# MicrophoneArray.net
KiCad netlist of a schematic drawn in Altium Designer
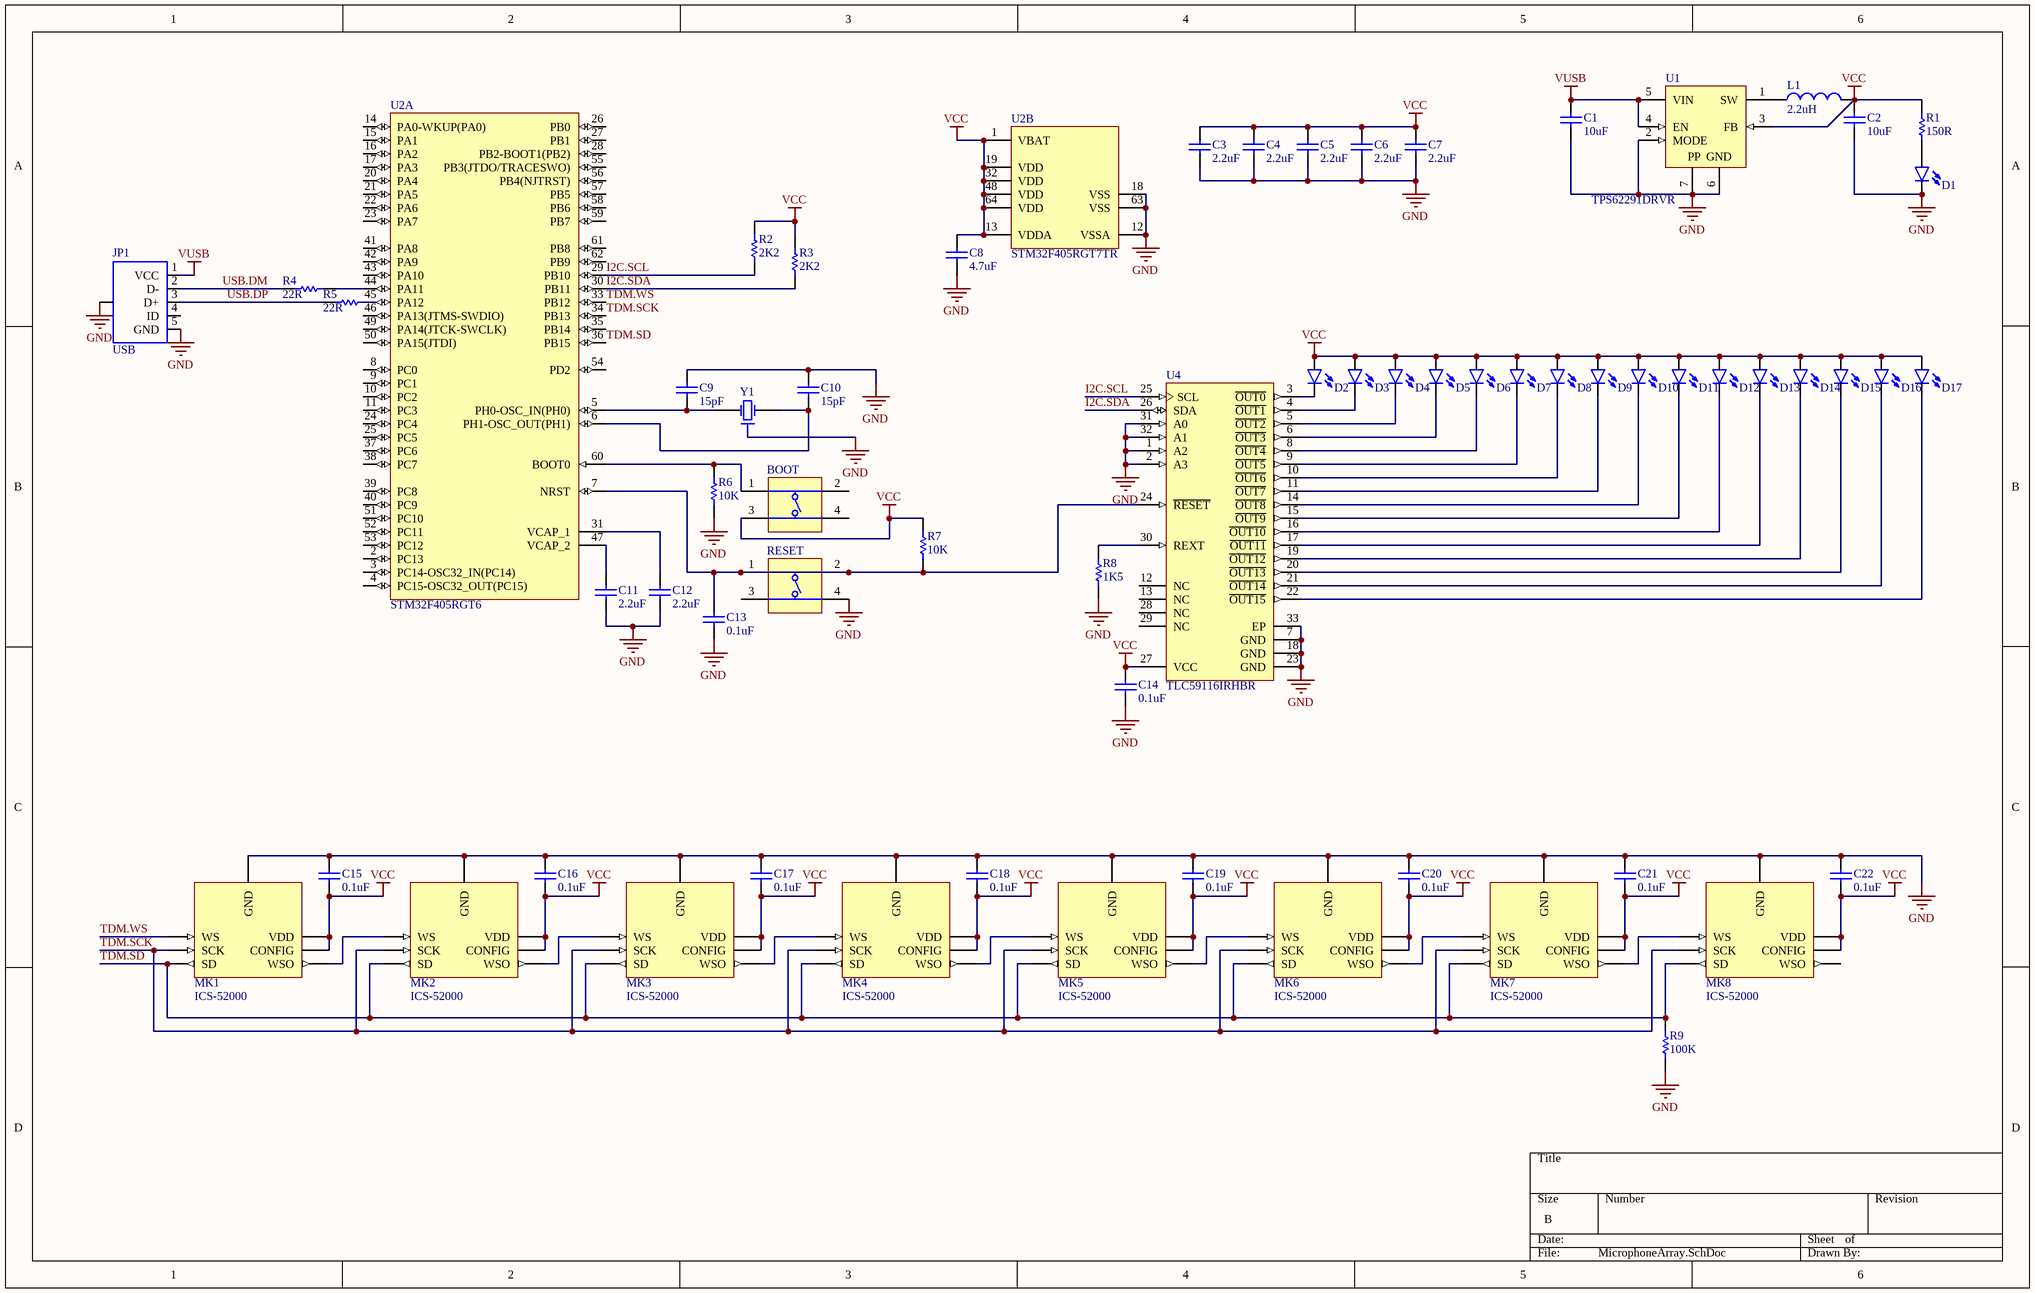
[diagram p0: MicrophoneArray.SchDoc]

(export (version "E")
  (design (tool "Eeschema 10.0.6"))
  (components
    (comp (ref "BOOT")
      (value "~")
      (footprint "SWITCH")
      (description "Switch, SPNO Push Button SMD")
      (fields
        (field (name "MANUFACTURER") "C&K Components")
        (field (name "PARTNUMBER") "PTS810 SJM 250 SMTR LFS")
      )
      (libsource (lib "Components") (part "DIPT-DTSM-6"))
    )
    (comp (ref "C1")
      (value "10uF")
      (footprint "C0402[1005X55]")
      (description "10uF 6.3V 20% 0402 (1005 Metric)")
      (fields (field (name "TOLERANCE") "20%") (field (name "PARTNUMBER") "GRM155R60J106ME44D"))
      (libsource (lib "Capacitors") (part "CAP_10uF_6.3V_0402_20%"))
    )
    (comp (ref "C2")
      (value "10uF")
      (footprint "C0402[1005X55]")
      (description "10uF 6.3V 20% 0402 (1005 Metric)")
      (fields (field (name "TOLERANCE") "20%") (field (name "PARTNUMBER") "GRM155R60J106ME44D"))
      (libsource (lib "Capacitors") (part "CAP_10uF_6.3V_0402_20%"))
    )
    (comp (ref "C3")
      (value "2.2uF")
      (footprint "C0402[1005X55]")
      (description "2.2uF 6.3V 20% 0402 (1005 Metric)")
      (fields (field (name "TOLERANCE") "20%") (field (name "PARTNUMBER") "GRM155R60J225ME15D"))
      (libsource (lib "Capacitors") (part "CAP_2.2uF_6.3V_0402_20%"))
    )
    (comp (ref "C4")
      (value "2.2uF")
      (footprint "C0402[1005X55]")
      (description "2.2uF 6.3V 20% 0402 (1005 Metric)")
      (fields (field (name "TOLERANCE") "20%") (field (name "PARTNUMBER") "GRM155R60J225ME15D"))
      (libsource (lib "Capacitors") (part "CAP_2.2uF_6.3V_0402_20%"))
    )
    (comp (ref "C5")
      (value "2.2uF")
      (footprint "C0402[1005X55]")
      (description "2.2uF 6.3V 20% 0402 (1005 Metric)")
      (fields (field (name "TOLERANCE") "20%") (field (name "PARTNUMBER") "GRM155R60J225ME15D"))
      (libsource (lib "Capacitors") (part "CAP_2.2uF_6.3V_0402_20%"))
    )
    (comp (ref "C6")
      (value "2.2uF")
      (footprint "C0402[1005X55]")
      (description "2.2uF 6.3V 20% 0402 (1005 Metric)")
      (fields (field (name "TOLERANCE") "20%") (field (name "PARTNUMBER") "GRM155R60J225ME15D"))
      (libsource (lib "Capacitors") (part "CAP_2.2uF_6.3V_0402_20%"))
    )
    (comp (ref "C7")
      (value "2.2uF")
      (footprint "C0402[1005X55]")
      (description "2.2uF 6.3V 20% 0402 (1005 Metric)")
      (fields (field (name "TOLERANCE") "20%") (field (name "PARTNUMBER") "GRM155R60J225ME15D"))
      (libsource (lib "Capacitors") (part "CAP_2.2uF_6.3V_0402_20%"))
    )
    (comp (ref "C8")
      (value "4.7uF")
      (footprint "C0402[1005X55]")
      (description "4.7uF 6.3V 20% 0402 (1005 Metric)")
      (fields (field (name "TOLERANCE") "20%") (field (name "PARTNUMBER") "GRM155R60J475ME47D"))
      (libsource (lib "Capacitors") (part "CAP_4.7uF_6.3V_0402_20%"))
    )
    (comp (ref "C9")
      (value "15pF")
      (footprint "C0402[1005X55]")
      (description "15pF 50V 5% 0402 (1005 Metric)")
      (fields (field (name "TOLERANCE") "5%") (field (name "PARTNUMBER") "GRM1555C1H150JA01D"))
      (libsource (lib "Capacitors") (part "CAP_15pF_50V_0402_5%"))
    )
    (comp (ref "C10")
      (value "15pF")
      (footprint "C0402[1005X55]")
      (description "15pF 50V 5% 0402 (1005 Metric)")
      (fields (field (name "TOLERANCE") "5%") (field (name "PARTNUMBER") "GRM1555C1H150JA01D"))
      (libsource (lib "Capacitors") (part "CAP_15pF_50V_0402_5%"))
    )
    (comp (ref "C11")
      (value "2.2uF")
      (footprint "C0402[1005X55]")
      (description "2.2uF 6.3V 20% 0402 (1005 Metric)")
      (fields (field (name "TOLERANCE") "20%") (field (name "PARTNUMBER") "GRM155R60J225ME15D"))
      (libsource (lib "Capacitors") (part "CAP_2.2uF_6.3V_0402_20%"))
    )
    (comp (ref "C12")
      (value "2.2uF")
      (footprint "C0402[1005X55]")
      (description "2.2uF 6.3V 20% 0402 (1005 Metric)")
      (fields (field (name "TOLERANCE") "20%") (field (name "PARTNUMBER") "GRM155R60J225ME15D"))
      (libsource (lib "Capacitors") (part "CAP_2.2uF_6.3V_0402_20%"))
    )
    (comp (ref "C13")
      (value "0.1uF")
      (footprint "C0402[1005X55]")
      (description "0.1uF 6.3V 10% 0402 (1005 Metric)")
      (fields (field (name "TOLERANCE") "10%") (field (name "PARTNUMBER") "GRM155R70J104KA01D"))
      (libsource (lib "Capacitors") (part "CAP_0.1uF_6.3V_0402_10%"))
    )
    (comp (ref "C14")
      (value "0.1uF")
      (footprint "C0402[1005X55]")
      (description "0.1uF 6.3V 10% 0402 (1005 Metric)")
      (fields (field (name "PARTNUMBER") "GRM155R70J104KA01D") (field (name "MANUFACTURER") "Murata"))
      (libsource (lib "Capacitors") (part "CAP_0.1uF_6.3V_0402_10%"))
    )
    (comp (ref "C15")
      (value "0.1uF")
      (footprint "C0402[1005X55]")
      (description "0.1uF 6.3V 10% 0402 (1005 Metric)")
      (fields (field (name "PARTNUMBER") "GRM155R70J104KA01D") (field (name "MANUFACTURER") "Murata"))
      (libsource (lib "Capacitors") (part "CAP_0.1uF_6.3V_0402_10%"))
    )
    (comp (ref "C16")
      (value "0.1uF")
      (footprint "C0402[1005X55]")
      (description "0.1uF 6.3V 10% 0402 (1005 Metric)")
      (fields (field (name "PARTNUMBER") "GRM155R70J104KA01D") (field (name "MANUFACTURER") "Murata"))
      (libsource (lib "Capacitors") (part "CAP_0.1uF_6.3V_0402_10%"))
    )
    (comp (ref "C17")
      (value "0.1uF")
      (footprint "C0402[1005X55]")
      (description "0.1uF 6.3V 10% 0402 (1005 Metric)")
      (fields (field (name "PARTNUMBER") "GRM155R70J104KA01D") (field (name "MANUFACTURER") "Murata"))
      (libsource (lib "Capacitors") (part "CAP_0.1uF_6.3V_0402_10%"))
    )
    (comp (ref "C18")
      (value "0.1uF")
      (footprint "C0402[1005X55]")
      (description "0.1uF 6.3V 10% 0402 (1005 Metric)")
      (fields (field (name "PARTNUMBER") "GRM155R70J104KA01D") (field (name "MANUFACTURER") "Murata"))
      (libsource (lib "Capacitors") (part "CAP_0.1uF_6.3V_0402_10%"))
    )
    (comp (ref "C19")
      (value "0.1uF")
      (footprint "C0402[1005X55]")
      (description "0.1uF 6.3V 10% 0402 (1005 Metric)")
      (fields (field (name "PARTNUMBER") "GRM155R70J104KA01D") (field (name "MANUFACTURER") "Murata"))
      (libsource (lib "Capacitors") (part "CAP_0.1uF_6.3V_0402_10%"))
    )
    (comp (ref "C20")
      (value "0.1uF")
      (footprint "C0402[1005X55]")
      (description "0.1uF 6.3V 10% 0402 (1005 Metric)")
      (fields (field (name "PARTNUMBER") "GRM155R70J104KA01D") (field (name "MANUFACTURER") "Murata"))
      (libsource (lib "Capacitors") (part "CAP_0.1uF_6.3V_0402_10%"))
    )
    (comp (ref "C21")
      (value "0.1uF")
      (footprint "C0402[1005X55]")
      (description "0.1uF 6.3V 10% 0402 (1005 Metric)")
      (fields (field (name "PARTNUMBER") "GRM155R70J104KA01D") (field (name "MANUFACTURER") "Murata"))
      (libsource (lib "Capacitors") (part "CAP_0.1uF_6.3V_0402_10%"))
    )
    (comp (ref "C22")
      (value "0.1uF")
      (footprint "C0402[1005X55]")
      (description "0.1uF 6.3V 10% 0402 (1005 Metric)")
      (fields (field (name "PARTNUMBER") "GRM155R70J104KA01D") (field (name "MANUFACTURER") "Murata"))
      (libsource (lib "Capacitors") (part "CAP_0.1uF_6.3V_0402_10%"))
    )
    (comp (ref "D1")
      (value "LED_0603_GREEN_5mA")
      (footprint "LED0603")
      (fields (field (name "PARTNUMBER") "LTST-C193TGKT-5A") (field (name "MANUFACTURER") "Lite-On Inc."))
      (libsource (lib "LEDs") (part "LED_0603_GREEN_5mA"))
    )
    (comp (ref "D2")
      (value "LED_0603_BLUE_5mA")
      (footprint "LED0603")
      (fields (field (name "PARTNUMBER") "LTST-C193TBKT-5A") (field (name "MANUFACTURER") "Lite-On Inc."))
      (libsource (lib "LEDs") (part "LED_0603_BLUE_5mA"))
    )
    (comp (ref "D3")
      (value "LED_0603_BLUE_5mA")
      (footprint "LED0603")
      (fields (field (name "PARTNUMBER") "LTST-C193TBKT-5A") (field (name "MANUFACTURER") "Lite-On Inc."))
      (libsource (lib "LEDs") (part "LED_0603_BLUE_5mA"))
    )
    (comp (ref "D4")
      (value "LED_0603_BLUE_5mA")
      (footprint "LED0603")
      (fields (field (name "PARTNUMBER") "LTST-C193TBKT-5A") (field (name "MANUFACTURER") "Lite-On Inc."))
      (libsource (lib "LEDs") (part "LED_0603_BLUE_5mA"))
    )
    (comp (ref "D5")
      (value "LED_0603_BLUE_5mA")
      (footprint "LED0603")
      (fields (field (name "PARTNUMBER") "LTST-C193TBKT-5A") (field (name "MANUFACTURER") "Lite-On Inc."))
      (libsource (lib "LEDs") (part "LED_0603_BLUE_5mA"))
    )
    (comp (ref "D6")
      (value "LED_0603_BLUE_5mA")
      (footprint "LED0603")
      (fields (field (name "PARTNUMBER") "LTST-C193TBKT-5A") (field (name "MANUFACTURER") "Lite-On Inc."))
      (libsource (lib "LEDs") (part "LED_0603_BLUE_5mA"))
    )
    (comp (ref "D7")
      (value "LED_0603_BLUE_5mA")
      (footprint "LED0603")
      (fields (field (name "PARTNUMBER") "LTST-C193TBKT-5A") (field (name "MANUFACTURER") "Lite-On Inc."))
      (libsource (lib "LEDs") (part "LED_0603_BLUE_5mA"))
    )
    (comp (ref "D8")
      (value "LED_0603_BLUE_5mA")
      (footprint "LED0603")
      (fields (field (name "PARTNUMBER") "LTST-C193TBKT-5A") (field (name "MANUFACTURER") "Lite-On Inc."))
      (libsource (lib "LEDs") (part "LED_0603_BLUE_5mA"))
    )
    (comp (ref "D9")
      (value "LED_0603_BLUE_5mA")
      (footprint "LED0603")
      (fields (field (name "PARTNUMBER") "LTST-C193TBKT-5A") (field (name "MANUFACTURER") "Lite-On Inc."))
      (libsource (lib "LEDs") (part "LED_0603_BLUE_5mA"))
    )
    (comp (ref "D10")
      (value "LED_0603_BLUE_5mA")
      (footprint "LED0603")
      (fields (field (name "PARTNUMBER") "LTST-C193TBKT-5A") (field (name "MANUFACTURER") "Lite-On Inc."))
      (libsource (lib "LEDs") (part "LED_0603_BLUE_5mA"))
    )
    (comp (ref "D11")
      (value "LED_0603_BLUE_5mA")
      (footprint "LED0603")
      (fields (field (name "PARTNUMBER") "LTST-C193TBKT-5A") (field (name "MANUFACTURER") "Lite-On Inc."))
      (libsource (lib "LEDs") (part "LED_0603_BLUE_5mA"))
    )
    (comp (ref "D12")
      (value "LED_0603_BLUE_5mA")
      (footprint "LED0603")
      (fields (field (name "PARTNUMBER") "LTST-C193TBKT-5A") (field (name "MANUFACTURER") "Lite-On Inc."))
      (libsource (lib "LEDs") (part "LED_0603_BLUE_5mA"))
    )
    (comp (ref "D13")
      (value "LED_0603_BLUE_5mA")
      (footprint "LED0603")
      (fields (field (name "PARTNUMBER") "LTST-C193TBKT-5A") (field (name "MANUFACTURER") "Lite-On Inc."))
      (libsource (lib "LEDs") (part "LED_0603_BLUE_5mA"))
    )
    (comp (ref "D14")
      (value "LED_0603_BLUE_5mA")
      (footprint "LED0603")
      (fields (field (name "PARTNUMBER") "LTST-C193TBKT-5A") (field (name "MANUFACTURER") "Lite-On Inc."))
      (libsource (lib "LEDs") (part "LED_0603_BLUE_5mA"))
    )
    (comp (ref "D15")
      (value "LED_0603_BLUE_5mA")
      (footprint "LED0603")
      (fields (field (name "PARTNUMBER") "LTST-C193TBKT-5A") (field (name "MANUFACTURER") "Lite-On Inc."))
      (libsource (lib "LEDs") (part "LED_0603_BLUE_5mA"))
    )
    (comp (ref "D16")
      (value "LED_0603_BLUE_5mA")
      (footprint "LED0603")
      (fields (field (name "PARTNUMBER") "LTST-C193TBKT-5A") (field (name "MANUFACTURER") "Lite-On Inc."))
      (libsource (lib "LEDs") (part "LED_0603_BLUE_5mA"))
    )
    (comp (ref "D17")
      (value "LED_0603_BLUE_5mA")
      (footprint "LED0603")
      (fields (field (name "PARTNUMBER") "LTST-C193TBKT-5A") (field (name "MANUFACTURER") "Lite-On Inc."))
      (libsource (lib "LEDs") (part "LED_0603_BLUE_5mA"))
    )
    (comp (ref "JP1")
      (value "USB")
      (footprint "USB-MICROB")
      (fields (field (name "PARTNUMBER") "10118192-0001LF") (field (name "MANUFACTURER") "Amphenol FCI"))
      (libsource (lib "Connectors") (part "USB_MICROB_SMT"))
    )
    (comp (ref "L1")
      (value "2.2uH")
      (footprint "IND0805")
      (description "2.2uH 20% 1.7A 0805")
      (fields (field (name "PARTNUMBER") "LQM21PN2R2MGHL") (field (name "MANUFACTURER") "Murata"))
      (libsource (lib "Inductors") (part "IND_2.2uH_1.7A_0805_20%"))
    )
    (comp (ref "MK1")
      (value "ICS-52000")
      (footprint "MIC")
      (description "MIC MEMS DIGITAL OMNI -26DB")
      (fields (field (name "MANUFACTURER") "TDK InvenSense"))
      (libsource (lib "Components") (part "ICS-52000"))
    )
    (comp (ref "MK2")
      (value "ICS-52000")
      (footprint "MIC")
      (description "MIC MEMS DIGITAL OMNI -26DB")
      (fields (field (name "MANUFACTURER") "TDK InvenSense"))
      (libsource (lib "Components") (part "ICS-52000"))
    )
    (comp (ref "MK3")
      (value "ICS-52000")
      (footprint "MIC")
      (description "MIC MEMS DIGITAL OMNI -26DB")
      (fields (field (name "MANUFACTURER") "TDK InvenSense"))
      (libsource (lib "Components") (part "ICS-52000"))
    )
    (comp (ref "MK4")
      (value "ICS-52000")
      (footprint "MIC")
      (description "MIC MEMS DIGITAL OMNI -26DB")
      (fields (field (name "MANUFACTURER") "TDK InvenSense"))
      (libsource (lib "Components") (part "ICS-52000"))
    )
    (comp (ref "MK5")
      (value "ICS-52000")
      (footprint "MIC")
      (description "MIC MEMS DIGITAL OMNI -26DB")
      (fields (field (name "MANUFACTURER") "TDK InvenSense"))
      (libsource (lib "Components") (part "ICS-52000"))
    )
    (comp (ref "MK6")
      (value "ICS-52000")
      (footprint "MIC")
      (description "MIC MEMS DIGITAL OMNI -26DB")
      (fields (field (name "MANUFACTURER") "TDK InvenSense"))
      (libsource (lib "Components") (part "ICS-52000"))
    )
    (comp (ref "MK7")
      (value "ICS-52000")
      (footprint "MIC")
      (description "MIC MEMS DIGITAL OMNI -26DB")
      (fields (field (name "MANUFACTURER") "TDK InvenSense"))
      (libsource (lib "Components") (part "ICS-52000"))
    )
    (comp (ref "MK8")
      (value "ICS-52000")
      (footprint "MIC")
      (description "MIC MEMS DIGITAL OMNI -26DB")
      (fields (field (name "MANUFACTURER") "TDK InvenSense"))
      (libsource (lib "Components") (part "ICS-52000"))
    )
    (comp (ref "R1")
      (value "150R")
      (footprint "R0402[1005]")
      (description "150R 0.063W 1% 0402 (1005 Metric)")
      (fields (field (name "MANUFACTURER") "KOA Speer") (field (name "PARTNUMBER") "RK73H1ETTP1500F"))
      (libsource (lib "Resistors") (part "RES_150R_0402_1%"))
    )
    (comp (ref "R2")
      (value "2K2")
      (footprint "R0402[1005]")
      (description "2K2 0.063W 1% 0402 (1005 Metric)")
      (fields (field (name "TOLERANCE") "1%") (field (name "POWER") "0.063W"))
      (libsource (lib "Resistors") (part "RES_2K2_0402_1%"))
    )
    (comp (ref "R3")
      (value "2K2")
      (footprint "R0402[1005]")
      (description "2K2 0.063W 1% 0402 (1005 Metric)")
      (fields (field (name "TOLERANCE") "1%") (field (name "POWER") "0.063W"))
      (libsource (lib "Resistors") (part "RES_2K2_0402_1%"))
    )
    (comp (ref "R4")
      (value "22R")
      (footprint "R0402[1005]")
      (description "22R 0.063W 1% 0402 (1005 Metric)")
      (fields (field (name "POWER") "0.063W") (field (name "TOLERANCE") "1%"))
      (libsource (lib "Resistors") (part "RES_22R_0402_1%"))
    )
    (comp (ref "R5")
      (value "22R")
      (footprint "R0402[1005]")
      (description "22R 0.063W 1% 0402 (1005 Metric)")
      (fields (field (name "POWER") "0.063W") (field (name "TOLERANCE") "1%"))
      (libsource (lib "Resistors") (part "RES_22R_0402_1%"))
    )
    (comp (ref "R6")
      (value "10K")
      (footprint "R0402[1005]")
      (description "10K 0.063W 1% 0402 (1005 Metric)")
      (fields (field (name "TOLERANCE") "1%") (field (name "POWER") "0.063W"))
      (libsource (lib "Resistors") (part "RES_10K_0402_1%"))
    )
    (comp (ref "R7")
      (value "10K")
      (footprint "R0402[1005]")
      (description "10K 0.063W 1% 0402 (1005 Metric)")
      (fields (field (name "MANUFACTURER") "KOA Speer") (field (name "PARTNUMBER") "RK73H1ETTP1002F"))
      (libsource (lib "Resistors") (part "RES_10K_0402_1%"))
    )
    (comp (ref "R8")
      (value "1K5")
      (footprint "R0402[1005]")
      (description "1K5 0.063W 1% 0402 (1005 Metric)")
      (fields (field (name "MANUFACTURER") "KOA Speer") (field (name "PARTNUMBER") "RK73H1ETTP1501F"))
      (libsource (lib "Resistors") (part "RES_1K5_0402_1%"))
    )
    (comp (ref "R9")
      (value "100K")
      (footprint "R0402[1005]")
      (description "100K 0.063W 1% 0402 (1005 Metric)")
      (fields (field (name "MANUFACTURER") "KOA Speer") (field (name "PARTNUMBER") "RK73H1ETTP1003F"))
      (libsource (lib "Resistors") (part "RES_100K_0402_1%"))
    )
    (comp (ref "RESET")
      (value "~")
      (footprint "SWITCH")
      (description "Switch, SPNO Push Button SMD")
      (fields
        (field (name "MANUFACTURER") "C&K Components")
        (field (name "PARTNUMBER") "PTS810 SJM 250 SMTR LFS")
      )
      (libsource (lib "Components") (part "DIPT-DTSM-6"))
    )
    (comp (ref "U1")
      (value "TPS62291DRVR")
      (footprint "WSON-6")
      (description "Voltage Regulators - Switching Regulators 2.25MHz 1A Step-Down Cnvrtr 3.3V Output")
      (fields (field (name "MANUFACTURER") "Texas Instruments"))
      (libsource (lib "ICs") (part "TPS62291DRVR"))
    )
    (comp (ref "U2")
      (value "STM32F405RGT6")
      (footprint "STM-LQFP64_L")
      (fields (field (name "MANUFACTURER") "STMicroelectronics"))
      (libsource (lib "Altium Content Vault") (part "CMP-0243-00089-2"))
    )
    (comp (ref "U4")
      (value "TLC59116IRHBR")
      (footprint "RHB0032E_V")
      (fields (field (name "MANUFACTURER") "Texas Instruments"))
      (libsource (lib "Altium Content Vault") (part "TI-TLC59116RHB32-3450X3450TP"))
    )
    (comp (ref "Y1")
      (value "~")
      (footprint "ABRA-ABM3B-4_V")
      (fields (field (name "PARTNUMBER") "ABM3B-8.000MHZ-10-1UT") (field (name "MANUFACTURER") "ABRACON"))
      (libsource (lib "Components") (part "ABRA-ABM3B-4"))
    )
  )
  (nets
    (net (code "1") (name "/I2C.SCL") (class "Default")
      (node (ref "R2") (pin "1") (pinfunction "1_1") (pintype "passive"))
      (node (ref "U2") (pin "29") (pinfunction "PB10_29") (pintype "bidirectional"))
      (node (ref "U4") (pin "25") (pinfunction "SCL_25") (pintype "input"))
    )
    (net (code "2") (name "/I2C.SDA") (class "Default")
      (node (ref "R3") (pin "1") (pinfunction "1_1") (pintype "passive"))
      (node (ref "U2") (pin "30") (pinfunction "PB11_30") (pintype "bidirectional"))
      (node (ref "U4") (pin "26") (pinfunction "SDA_26") (pintype "bidirectional"))
    )
    (net (code "3") (name "/TDM.SCK") (class "Default")
      (node (ref "MK1") (pin "6") (pinfunction "SCK_6") (pintype "input"))
      (node (ref "MK2") (pin "6") (pinfunction "SCK_6") (pintype "input"))
      (node (ref "MK3") (pin "6") (pinfunction "SCK_6") (pintype "input"))
      (node (ref "MK4") (pin "6") (pinfunction "SCK_6") (pintype "input"))
      (node (ref "MK5") (pin "6") (pinfunction "SCK_6") (pintype "input"))
      (node (ref "MK6") (pin "6") (pinfunction "SCK_6") (pintype "input"))
      (node (ref "MK7") (pin "6") (pinfunction "SCK_6") (pintype "input"))
      (node (ref "MK8") (pin "6") (pinfunction "SCK_6") (pintype "input"))
      (node (ref "U2") (pin "34") (pinfunction "PB13_34") (pintype "bidirectional"))
    )
    (net (code "4") (name "/TDM.SD") (class "Default")
      (node (ref "MK1") (pin "7") (pinfunction "SD_7") (pintype "output"))
      (node (ref "MK2") (pin "7") (pinfunction "SD_7") (pintype "output"))
      (node (ref "MK3") (pin "7") (pinfunction "SD_7") (pintype "output"))
      (node (ref "MK4") (pin "7") (pinfunction "SD_7") (pintype "output"))
      (node (ref "MK5") (pin "7") (pinfunction "SD_7") (pintype "output"))
      (node (ref "MK6") (pin "7") (pinfunction "SD_7") (pintype "output"))
      (node (ref "MK7") (pin "7") (pinfunction "SD_7") (pintype "output"))
      (node (ref "MK8") (pin "7") (pinfunction "SD_7") (pintype "output"))
      (node (ref "R9") (pin "2") (pinfunction "2_2") (pintype "passive"))
      (node (ref "U2") (pin "36") (pinfunction "PB15_36") (pintype "bidirectional"))
    )
    (net (code "5") (name "/TDM.WS") (class "Default")
      (node (ref "MK1") (pin "5") (pinfunction "WS_5") (pintype "input"))
      (node (ref "U2") (pin "33") (pinfunction "PB12_33") (pintype "bidirectional"))
    )
    (net (code "6") (name "/USB.DM") (class "Default")
      (node (ref "JP1") (pin "2") (pinfunction "D-_2") (pintype "passive"))
      (node (ref "R4") (pin "1") (pinfunction "1_1") (pintype "passive"))
    )
    (net (code "7") (name "/USB.DP") (class "Default")
      (node (ref "JP1") (pin "3") (pinfunction "D+_3") (pintype "passive"))
      (node (ref "R5") (pin "1") (pinfunction "1_1") (pintype "passive"))
    )
    (net (code "8") (name "GND") (class "Default")
      (node (ref "C1") (pin "1") (pinfunction "1_1") (pintype "passive"))
      (node (ref "C10") (pin "2") (pinfunction "2_2") (pintype "passive"))
      (node (ref "C11") (pin "1") (pinfunction "1_1") (pintype "passive"))
      (node (ref "C12") (pin "1") (pinfunction "1_1") (pintype "passive"))
      (node (ref "C13") (pin "1") (pinfunction "1_1") (pintype "passive"))
      (node (ref "C14") (pin "1") (pinfunction "1_1") (pintype "passive"))
      (node (ref "C15") (pin "2") (pinfunction "2_2") (pintype "passive"))
      (node (ref "C16") (pin "2") (pinfunction "2_2") (pintype "passive"))
      (node (ref "C17") (pin "2") (pinfunction "2_2") (pintype "passive"))
      (node (ref "C18") (pin "2") (pinfunction "2_2") (pintype "passive"))
      (node (ref "C19") (pin "2") (pinfunction "2_2") (pintype "passive"))
      (node (ref "C2") (pin "1") (pinfunction "1_1") (pintype "passive"))
      (node (ref "C20") (pin "2") (pinfunction "2_2") (pintype "passive"))
      (node (ref "C21") (pin "2") (pinfunction "2_2") (pintype "passive"))
      (node (ref "C22") (pin "2") (pinfunction "2_2") (pintype "passive"))
      (node (ref "C3") (pin "1") (pinfunction "1_1") (pintype "passive"))
      (node (ref "C4") (pin "1") (pinfunction "1_1") (pintype "passive"))
      (node (ref "C5") (pin "1") (pinfunction "1_1") (pintype "passive"))
      (node (ref "C6") (pin "1") (pinfunction "1_1") (pintype "passive"))
      (node (ref "C7") (pin "1") (pinfunction "1_1") (pintype "passive"))
      (node (ref "C8") (pin "1") (pinfunction "1_1") (pintype "passive"))
      (node (ref "C9") (pin "2") (pinfunction "2_2") (pintype "passive"))
      (node (ref "D1") (pin "C") (pinfunction "C_C") (pintype "passive"))
      (node (ref "JP1") (pin "5") (pinfunction "GND_5") (pintype "passive"))
      (node (ref "JP1") (pin "6") (pinfunction "SHIELD_6") (pintype "passive"))
      (node (ref "MK1") (pin "4") (pinfunction "GND_4") (pintype "power_in"))
      (node (ref "MK2") (pin "4") (pinfunction "GND_4") (pintype "power_in"))
      (node (ref "MK3") (pin "4") (pinfunction "GND_4") (pintype "power_in"))
      (node (ref "MK4") (pin "4") (pinfunction "GND_4") (pintype "power_in"))
      (node (ref "MK5") (pin "4") (pinfunction "GND_4") (pintype "power_in"))
      (node (ref "MK6") (pin "4") (pinfunction "GND_4") (pintype "power_in"))
      (node (ref "MK7") (pin "4") (pinfunction "GND_4") (pintype "power_in"))
      (node (ref "MK8") (pin "4") (pinfunction "GND_4") (pintype "power_in"))
      (node (ref "R6") (pin "1") (pinfunction "1_1") (pintype "passive"))
      (node (ref "R8") (pin "1") (pinfunction "1_1") (pintype "passive"))
      (node (ref "R9") (pin "1") (pinfunction "1_1") (pintype "passive"))
      (node (ref "RESET") (pin "4") (pinfunction "T3_4") (pintype "passive"))
      (node (ref "U1") (pin "2") (pinfunction "MODE_2") (pintype "input"))
      (node (ref "U1") (pin "6") (pinfunction "GND_6") (pintype "power_in"))
      (node (ref "U1") (pin "7") (pinfunction "EP_7") (pintype "passive"))
      (node (ref "U2") (pin "12") (pinfunction "VSSA_12") (pintype "power_in"))
      (node (ref "U2") (pin "18") (pinfunction "VSS_18") (pintype "power_in"))
      (node (ref "U2") (pin "63") (pinfunction "VSS_63") (pintype "power_in"))
      (node (ref "U4") (pin "1") (pinfunction "A2_1") (pintype "input"))
      (node (ref "U4") (pin "18") (pinfunction "GND_18") (pintype "power_in"))
      (node (ref "U4") (pin "2") (pinfunction "A3_2") (pintype "input"))
      (node (ref "U4") (pin "23") (pinfunction "GND_23") (pintype "power_in"))
      (node (ref "U4") (pin "31") (pinfunction "A0_31") (pintype "input"))
      (node (ref "U4") (pin "32") (pinfunction "A1_32") (pintype "input"))
      (node (ref "U4") (pin "33") (pinfunction "EP_33") (pintype "power_in"))
      (node (ref "U4") (pin "7") (pinfunction "GND_7") (pintype "power_in"))
      (node (ref "Y1") (pin "2") (pinfunction "2_2") (pintype "passive"))
    )
    (net (code "9") (name "Net-(BOOT-T1)") (class "Default")
      (node (ref "BOOT") (pin "1") (pinfunction "T1_1") (pintype "passive"))
      (node (ref "R6") (pin "2") (pinfunction "2_2") (pintype "passive"))
      (node (ref "U2") (pin "60") (pinfunction "BOOT0_60") (pintype "input"))
    )
    (net (code "10") (name "Net-(D1-PadA)") (class "Default")
      (node (ref "D1") (pin "A") (pinfunction "A_A") (pintype "passive"))
      (node (ref "R1") (pin "1") (pinfunction "1_1") (pintype "passive"))
    )
    (net (code "11") (name "Net-(MK1-WSO)") (class "Default")
      (node (ref "MK1") (pin "1") (pinfunction "WSO_1") (pintype "output"))
      (node (ref "MK2") (pin "5") (pinfunction "WS_5") (pintype "input"))
    )
    (net (code "12") (name "Net-(MK2-WSO)") (class "Default")
      (node (ref "MK2") (pin "1") (pinfunction "WSO_1") (pintype "output"))
      (node (ref "MK3") (pin "5") (pinfunction "WS_5") (pintype "input"))
    )
    (net (code "13") (name "Net-(MK3-WSO)") (class "Default")
      (node (ref "MK3") (pin "1") (pinfunction "WSO_1") (pintype "output"))
      (node (ref "MK4") (pin "5") (pinfunction "WS_5") (pintype "input"))
    )
    (net (code "14") (name "Net-(MK4-WSO)") (class "Default")
      (node (ref "MK4") (pin "1") (pinfunction "WSO_1") (pintype "output"))
      (node (ref "MK5") (pin "5") (pinfunction "WS_5") (pintype "input"))
    )
    (net (code "15") (name "Net-(MK5-WSO)") (class "Default")
      (node (ref "MK5") (pin "1") (pinfunction "WSO_1") (pintype "output"))
      (node (ref "MK6") (pin "5") (pinfunction "WS_5") (pintype "input"))
    )
    (net (code "16") (name "Net-(MK6-WSO)") (class "Default")
      (node (ref "MK6") (pin "1") (pinfunction "WSO_1") (pintype "output"))
      (node (ref "MK7") (pin "5") (pinfunction "WS_5") (pintype "input"))
    )
    (net (code "17") (name "Net-(MK7-WSO)") (class "Default")
      (node (ref "MK7") (pin "1") (pinfunction "WSO_1") (pintype "output"))
      (node (ref "MK8") (pin "5") (pinfunction "WS_5") (pintype "input"))
    )
    (net (code "18") (name "Net-(RESET-T1)") (class "Default")
      (node (ref "C13") (pin "2") (pinfunction "2_2") (pintype "passive"))
      (node (ref "R7") (pin "1") (pinfunction "1_1") (pintype "passive"))
      (node (ref "RESET") (pin "1") (pinfunction "T1_1") (pintype "passive"))
      (node (ref "RESET") (pin "2") (pinfunction "T2_2") (pintype "passive"))
      (node (ref "U2") (pin "7") (pinfunction "NRST_7") (pintype "bidirectional"))
      (node (ref "U4") (pin "24") (pinfunction "~{RESET}_24") (pintype "input"))
    )
    (net (code "19") (name "Net-(U1-SW)") (class "Default")
      (node (ref "L1") (pin "1") (pinfunction "1_1") (pintype "passive"))
      (node (ref "U1") (pin "1") (pinfunction "SW_1") (pintype "power_in"))
    )
    (net (code "20") (name "Net-(U2A-PA11)") (class "Default")
      (node (ref "R4") (pin "2") (pinfunction "2_2") (pintype "passive"))
      (node (ref "U2") (pin "44") (pinfunction "PA11_44") (pintype "bidirectional"))
    )
    (net (code "21") (name "Net-(U2A-PA12)") (class "Default")
      (node (ref "R5") (pin "2") (pinfunction "2_2") (pintype "passive"))
      (node (ref "U2") (pin "45") (pinfunction "PA12_45") (pintype "bidirectional"))
    )
    (net (code "22") (name "Net-(U2A-PH0-OSC_IN(PH0))") (class "Default")
      (node (ref "C9") (pin "1") (pinfunction "1_1") (pintype "passive"))
      (node (ref "U2") (pin "5") (pinfunction "PH0-OSC_IN(PH0)_5") (pintype "bidirectional"))
      (node (ref "Y1") (pin "3") (pinfunction "X2_3") (pintype "passive"))
    )
    (net (code "23") (name "Net-(U2A-PH1-OSC_OUT(PH1))") (class "Default")
      (node (ref "C10") (pin "1") (pinfunction "1_1") (pintype "passive"))
      (node (ref "U2") (pin "6") (pinfunction "PH1-OSC_OUT(PH1)_6") (pintype "bidirectional"))
      (node (ref "Y1") (pin "1") (pinfunction "X1_1") (pintype "passive"))
    )
    (net (code "24") (name "Net-(U2A-VCAP_1)") (class "Default")
      (node (ref "C12") (pin "2") (pinfunction "2_2") (pintype "passive"))
      (node (ref "U2") (pin "31") (pinfunction "VCAP_1_31") (pintype "power_in"))
    )
    (net (code "25") (name "Net-(U2A-VCAP_2)") (class "Default")
      (node (ref "C11") (pin "2") (pinfunction "2_2") (pintype "passive"))
      (node (ref "U2") (pin "47") (pinfunction "VCAP_2_47") (pintype "power_in"))
    )
    (net (code "26") (name "Net-(U4-REXT)") (class "Default")
      (node (ref "R8") (pin "2") (pinfunction "2_2") (pintype "passive"))
      (node (ref "U4") (pin "30") (pinfunction "REXT_30") (pintype "input"))
    )
    (net (code "27") (name "Net-(U4-~{OUT0})") (class "Default")
      (node (ref "D2") (pin "C") (pinfunction "C_C") (pintype "passive"))
      (node (ref "U4") (pin "3") (pinfunction "~{OUT0}_3") (pintype "output"))
    )
    (net (code "28") (name "Net-(U4-~{OUT1})") (class "Default")
      (node (ref "D3") (pin "C") (pinfunction "C_C") (pintype "passive"))
      (node (ref "U4") (pin "4") (pinfunction "~{OUT1}_4") (pintype "output"))
    )
    (net (code "29") (name "Net-(U4-~{OUT2})") (class "Default")
      (node (ref "D4") (pin "C") (pinfunction "C_C") (pintype "passive"))
      (node (ref "U4") (pin "5") (pinfunction "~{OUT2}_5") (pintype "output"))
    )
    (net (code "30") (name "Net-(U4-~{OUT3})") (class "Default")
      (node (ref "D5") (pin "C") (pinfunction "C_C") (pintype "passive"))
      (node (ref "U4") (pin "6") (pinfunction "~{OUT3}_6") (pintype "output"))
    )
    (net (code "31") (name "Net-(U4-~{OUT4})") (class "Default")
      (node (ref "D6") (pin "C") (pinfunction "C_C") (pintype "passive"))
      (node (ref "U4") (pin "8") (pinfunction "~{OUT4}_8") (pintype "output"))
    )
    (net (code "32") (name "Net-(U4-~{OUT5})") (class "Default")
      (node (ref "D7") (pin "C") (pinfunction "C_C") (pintype "passive"))
      (node (ref "U4") (pin "9") (pinfunction "~{OUT5}_9") (pintype "output"))
    )
    (net (code "33") (name "Net-(U4-~{OUT6})") (class "Default")
      (node (ref "D8") (pin "C") (pinfunction "C_C") (pintype "passive"))
      (node (ref "U4") (pin "10") (pinfunction "~{OUT6}_10") (pintype "output"))
    )
    (net (code "34") (name "Net-(U4-~{OUT7})") (class "Default")
      (node (ref "D9") (pin "C") (pinfunction "C_C") (pintype "passive"))
      (node (ref "U4") (pin "11") (pinfunction "~{OUT7}_11") (pintype "output"))
    )
    (net (code "35") (name "Net-(U4-~{OUT8})") (class "Default")
      (node (ref "D10") (pin "C") (pinfunction "C_C") (pintype "passive"))
      (node (ref "U4") (pin "14") (pinfunction "~{OUT8}_14") (pintype "output"))
    )
    (net (code "36") (name "Net-(U4-~{OUT9})") (class "Default")
      (node (ref "D11") (pin "C") (pinfunction "C_C") (pintype "passive"))
      (node (ref "U4") (pin "15") (pinfunction "~{OUT9}_15") (pintype "output"))
    )
    (net (code "37") (name "Net-(U4-~{OUT10})") (class "Default")
      (node (ref "D12") (pin "C") (pinfunction "C_C") (pintype "passive"))
      (node (ref "U4") (pin "16") (pinfunction "~{OUT10}_16") (pintype "output"))
    )
    (net (code "38") (name "Net-(U4-~{OUT11})") (class "Default")
      (node (ref "D13") (pin "C") (pinfunction "C_C") (pintype "passive"))
      (node (ref "U4") (pin "17") (pinfunction "~{OUT11}_17") (pintype "output"))
    )
    (net (code "39") (name "Net-(U4-~{OUT12})") (class "Default")
      (node (ref "D14") (pin "C") (pinfunction "C_C") (pintype "passive"))
      (node (ref "U4") (pin "19") (pinfunction "~{OUT12}_19") (pintype "output"))
    )
    (net (code "40") (name "Net-(U4-~{OUT13})") (class "Default")
      (node (ref "D15") (pin "C") (pinfunction "C_C") (pintype "passive"))
      (node (ref "U4") (pin "20") (pinfunction "~{OUT13}_20") (pintype "output"))
    )
    (net (code "41") (name "Net-(U4-~{OUT14})") (class "Default")
      (node (ref "D16") (pin "C") (pinfunction "C_C") (pintype "passive"))
      (node (ref "U4") (pin "21") (pinfunction "~{OUT14}_21") (pintype "output"))
    )
    (net (code "42") (name "Net-(U4-~{OUT15})") (class "Default")
      (node (ref "D17") (pin "C") (pinfunction "C_C") (pintype "passive"))
      (node (ref "U4") (pin "22") (pinfunction "~{OUT15}_22") (pintype "output"))
    )
    (net (code "43") (name "VCC") (class "Default")
      (node (ref "BOOT") (pin "3") (pinfunction "T3_3") (pintype "passive"))
      (node (ref "C14") (pin "2") (pinfunction "2_2") (pintype "passive"))
      (node (ref "C15") (pin "1") (pinfunction "1_1") (pintype "passive"))
      (node (ref "C16") (pin "1") (pinfunction "1_1") (pintype "passive"))
      (node (ref "C17") (pin "1") (pinfunction "1_1") (pintype "passive"))
      (node (ref "C18") (pin "1") (pinfunction "1_1") (pintype "passive"))
      (node (ref "C19") (pin "1") (pinfunction "1_1") (pintype "passive"))
      (node (ref "C2") (pin "2") (pinfunction "2_2") (pintype "passive"))
      (node (ref "C20") (pin "1") (pinfunction "1_1") (pintype "passive"))
      (node (ref "C21") (pin "1") (pinfunction "1_1") (pintype "passive"))
      (node (ref "C22") (pin "1") (pinfunction "1_1") (pintype "passive"))
      (node (ref "C3") (pin "2") (pinfunction "2_2") (pintype "passive"))
      (node (ref "C4") (pin "2") (pinfunction "2_2") (pintype "passive"))
      (node (ref "C5") (pin "2") (pinfunction "2_2") (pintype "passive"))
      (node (ref "C6") (pin "2") (pinfunction "2_2") (pintype "passive"))
      (node (ref "C7") (pin "2") (pinfunction "2_2") (pintype "passive"))
      (node (ref "C8") (pin "2") (pinfunction "2_2") (pintype "passive"))
      (node (ref "D10") (pin "A") (pinfunction "A_A") (pintype "passive"))
      (node (ref "D11") (pin "A") (pinfunction "A_A") (pintype "passive"))
      (node (ref "D12") (pin "A") (pinfunction "A_A") (pintype "passive"))
      (node (ref "D13") (pin "A") (pinfunction "A_A") (pintype "passive"))
      (node (ref "D14") (pin "A") (pinfunction "A_A") (pintype "passive"))
      (node (ref "D15") (pin "A") (pinfunction "A_A") (pintype "passive"))
      (node (ref "D16") (pin "A") (pinfunction "A_A") (pintype "passive"))
      (node (ref "D17") (pin "A") (pinfunction "A_A") (pintype "passive"))
      (node (ref "D2") (pin "A") (pinfunction "A_A") (pintype "passive"))
      (node (ref "D3") (pin "A") (pinfunction "A_A") (pintype "passive"))
      (node (ref "D4") (pin "A") (pinfunction "A_A") (pintype "passive"))
      (node (ref "D5") (pin "A") (pinfunction "A_A") (pintype "passive"))
      (node (ref "D6") (pin "A") (pinfunction "A_A") (pintype "passive"))
      (node (ref "D7") (pin "A") (pinfunction "A_A") (pintype "passive"))
      (node (ref "D8") (pin "A") (pinfunction "A_A") (pintype "passive"))
      (node (ref "D9") (pin "A") (pinfunction "A_A") (pintype "passive"))
      (node (ref "L1") (pin "2") (pinfunction "2_2") (pintype "passive"))
      (node (ref "MK1") (pin "2") (pinfunction "CONFIG_2") (pintype "passive"))
      (node (ref "MK1") (pin "3") (pinfunction "VDD_3") (pintype "power_in"))
      (node (ref "MK2") (pin "2") (pinfunction "CONFIG_2") (pintype "passive"))
      (node (ref "MK2") (pin "3") (pinfunction "VDD_3") (pintype "power_in"))
      (node (ref "MK3") (pin "2") (pinfunction "CONFIG_2") (pintype "passive"))
      (node (ref "MK3") (pin "3") (pinfunction "VDD_3") (pintype "power_in"))
      (node (ref "MK4") (pin "2") (pinfunction "CONFIG_2") (pintype "passive"))
      (node (ref "MK4") (pin "3") (pinfunction "VDD_3") (pintype "power_in"))
      (node (ref "MK5") (pin "2") (pinfunction "CONFIG_2") (pintype "passive"))
      (node (ref "MK5") (pin "3") (pinfunction "VDD_3") (pintype "power_in"))
      (node (ref "MK6") (pin "2") (pinfunction "CONFIG_2") (pintype "passive"))
      (node (ref "MK6") (pin "3") (pinfunction "VDD_3") (pintype "power_in"))
      (node (ref "MK7") (pin "2") (pinfunction "CONFIG_2") (pintype "passive"))
      (node (ref "MK7") (pin "3") (pinfunction "VDD_3") (pintype "power_in"))
      (node (ref "MK8") (pin "2") (pinfunction "CONFIG_2") (pintype "passive"))
      (node (ref "MK8") (pin "3") (pinfunction "VDD_3") (pintype "power_in"))
      (node (ref "R1") (pin "2") (pinfunction "2_2") (pintype "passive"))
      (node (ref "R2") (pin "2") (pinfunction "2_2") (pintype "passive"))
      (node (ref "R3") (pin "2") (pinfunction "2_2") (pintype "passive"))
      (node (ref "R7") (pin "2") (pinfunction "2_2") (pintype "passive"))
      (node (ref "U1") (pin "3") (pinfunction "FB_3") (pintype "input"))
      (node (ref "U2") (pin "1") (pinfunction "VBAT_1") (pintype "power_in"))
      (node (ref "U2") (pin "13") (pinfunction "VDDA_13") (pintype "power_in"))
      (node (ref "U2") (pin "19") (pinfunction "VDD_19") (pintype "power_in"))
      (node (ref "U2") (pin "32") (pinfunction "VDD_32") (pintype "power_in"))
      (node (ref "U2") (pin "48") (pinfunction "VDD_48") (pintype "power_in"))
      (node (ref "U2") (pin "64") (pinfunction "VDD_64") (pintype "power_in"))
      (node (ref "U4") (pin "27") (pinfunction "VCC_27") (pintype "power_in"))
    )
    (net (code "44") (name "VUSB") (class "Default")
      (node (ref "C1") (pin "2") (pinfunction "2_2") (pintype "passive"))
      (node (ref "JP1") (pin "1") (pinfunction "VCC_1") (pintype "passive"))
      (node (ref "U1") (pin "4") (pinfunction "EN_4") (pintype "input"))
      (node (ref "U1") (pin "5") (pinfunction "VIN_5") (pintype "power_in"))
    )
    (net (code "45") (name "unconnected-(BOOT-T2-Pad2)") (class "Default")
      (node (ref "BOOT") (pin "2") (pinfunction "T2_2") (pintype "passive"))
    )
    (net (code "46") (name "unconnected-(BOOT-T3-Pad4)") (class "Default")
      (node (ref "BOOT") (pin "4") (pinfunction "T3_4") (pintype "passive"))
    )
    (net (code "47") (name "unconnected-(JP1-ID-Pad4)") (class "Default")
      (node (ref "JP1") (pin "4") (pinfunction "ID_4") (pintype "passive"))
    )
    (net (code "48") (name "unconnected-(MK8-WSO-Pad1)") (class "Default")
      (node (ref "MK8") (pin "1") (pinfunction "WSO_1") (pintype "output"))
    )
    (net (code "49") (name "unconnected-(RESET-T3-Pad3)") (class "Default")
      (node (ref "RESET") (pin "3") (pinfunction "T3_3") (pintype "passive"))
    )
    (net (code "50") (name "unconnected-(U2A-PA0-WKUP(PA0)-Pad14)") (class "Default")
      (node (ref "U2") (pin "14") (pinfunction "PA0-WKUP(PA0)_14") (pintype "bidirectional"))
    )
    (net (code "51") (name "unconnected-(U2A-PA1-Pad15)") (class "Default")
      (node (ref "U2") (pin "15") (pinfunction "PA1_15") (pintype "bidirectional"))
    )
    (net (code "52") (name "unconnected-(U2A-PA2-Pad16)") (class "Default")
      (node (ref "U2") (pin "16") (pinfunction "PA2_16") (pintype "bidirectional"))
    )
    (net (code "53") (name "unconnected-(U2A-PA3-Pad17)") (class "Default")
      (node (ref "U2") (pin "17") (pinfunction "PA3_17") (pintype "bidirectional"))
    )
    (net (code "54") (name "unconnected-(U2A-PA4-Pad20)") (class "Default")
      (node (ref "U2") (pin "20") (pinfunction "PA4_20") (pintype "bidirectional"))
    )
    (net (code "55") (name "unconnected-(U2A-PA5-Pad21)") (class "Default")
      (node (ref "U2") (pin "21") (pinfunction "PA5_21") (pintype "bidirectional"))
    )
    (net (code "56") (name "unconnected-(U2A-PA6-Pad22)") (class "Default")
      (node (ref "U2") (pin "22") (pinfunction "PA6_22") (pintype "bidirectional"))
    )
    (net (code "57") (name "unconnected-(U2A-PA7-Pad23)") (class "Default")
      (node (ref "U2") (pin "23") (pinfunction "PA7_23") (pintype "bidirectional"))
    )
    (net (code "58") (name "unconnected-(U2A-PA8-Pad41)") (class "Default")
      (node (ref "U2") (pin "41") (pinfunction "PA8_41") (pintype "bidirectional"))
    )
    (net (code "59") (name "unconnected-(U2A-PA9-Pad42)") (class "Default")
      (node (ref "U2") (pin "42") (pinfunction "PA9_42") (pintype "bidirectional"))
    )
    (net (code "60") (name "unconnected-(U2A-PA10-Pad43)") (class "Default")
      (node (ref "U2") (pin "43") (pinfunction "PA10_43") (pintype "bidirectional"))
    )
    (net (code "61") (name "unconnected-(U2A-PA13(JTMS-SWDIO)-Pad46)") (class "Default")
      (node (ref "U2") (pin "46") (pinfunction "PA13(JTMS-SWDIO)_46") (pintype "bidirectional"))
    )
    (net (code "62") (name "unconnected-(U2A-PA14(JTCK-SWCLK)-Pad49)") (class "Default")
      (node (ref "U2") (pin "49") (pinfunction "PA14(JTCK-SWCLK)_49") (pintype "bidirectional"))
    )
    (net (code "63") (name "unconnected-(U2A-PA15(JTDI)-Pad50)") (class "Default")
      (node (ref "U2") (pin "50") (pinfunction "PA15(JTDI)_50") (pintype "bidirectional"))
    )
    (net (code "64") (name "unconnected-(U2A-PB0-Pad26)") (class "Default")
      (node (ref "U2") (pin "26") (pinfunction "PB0_26") (pintype "bidirectional"))
    )
    (net (code "65") (name "unconnected-(U2A-PB1-Pad27)") (class "Default")
      (node (ref "U2") (pin "27") (pinfunction "PB1_27") (pintype "bidirectional"))
    )
    (net (code "66") (name "unconnected-(U2A-PB2-BOOT1(PB2)-Pad28)") (class "Default")
      (node (ref "U2") (pin "28") (pinfunction "PB2-BOOT1(PB2)_28") (pintype "bidirectional"))
    )
    (net (code "67") (name "unconnected-(U2A-PB3(JTDO{slash}TRACESWO)-Pad55)") (class "Default")
      (node (ref "U2") (pin "55") (pinfunction "PB3(JTDO/TRACESWO)_55") (pintype "bidirectional"))
    )
    (net (code "68") (name "unconnected-(U2A-PB4(NJTRST)-Pad56)") (class "Default")
      (node (ref "U2") (pin "56") (pinfunction "PB4(NJTRST)_56") (pintype "bidirectional"))
    )
    (net (code "69") (name "unconnected-(U2A-PB5-Pad57)") (class "Default")
      (node (ref "U2") (pin "57") (pinfunction "PB5_57") (pintype "bidirectional"))
    )
    (net (code "70") (name "unconnected-(U2A-PB6-Pad58)") (class "Default")
      (node (ref "U2") (pin "58") (pinfunction "PB6_58") (pintype "bidirectional"))
    )
    (net (code "71") (name "unconnected-(U2A-PB7-Pad59)") (class "Default")
      (node (ref "U2") (pin "59") (pinfunction "PB7_59") (pintype "bidirectional"))
    )
    (net (code "72") (name "unconnected-(U2A-PB8-Pad61)") (class "Default")
      (node (ref "U2") (pin "61") (pinfunction "PB8_61") (pintype "bidirectional"))
    )
    (net (code "73") (name "unconnected-(U2A-PB9-Pad62)") (class "Default")
      (node (ref "U2") (pin "62") (pinfunction "PB9_62") (pintype "bidirectional"))
    )
    (net (code "74") (name "unconnected-(U2A-PB14-Pad35)") (class "Default")
      (node (ref "U2") (pin "35") (pinfunction "PB14_35") (pintype "bidirectional"))
    )
    (net (code "75") (name "unconnected-(U2A-PC0-Pad8)") (class "Default")
      (node (ref "U2") (pin "8") (pinfunction "PC0_8") (pintype "bidirectional"))
    )
    (net (code "76") (name "unconnected-(U2A-PC1-Pad9)") (class "Default")
      (node (ref "U2") (pin "9") (pinfunction "PC1_9") (pintype "bidirectional"))
    )
    (net (code "77") (name "unconnected-(U2A-PC2-Pad10)") (class "Default")
      (node (ref "U2") (pin "10") (pinfunction "PC2_10") (pintype "bidirectional"))
    )
    (net (code "78") (name "unconnected-(U2A-PC3-Pad11)") (class "Default")
      (node (ref "U2") (pin "11") (pinfunction "PC3_11") (pintype "bidirectional"))
    )
    (net (code "79") (name "unconnected-(U2A-PC4-Pad24)") (class "Default")
      (node (ref "U2") (pin "24") (pinfunction "PC4_24") (pintype "bidirectional"))
    )
    (net (code "80") (name "unconnected-(U2A-PC5-Pad25)") (class "Default")
      (node (ref "U2") (pin "25") (pinfunction "PC5_25") (pintype "bidirectional"))
    )
    (net (code "81") (name "unconnected-(U2A-PC6-Pad37)") (class "Default")
      (node (ref "U2") (pin "37") (pinfunction "PC6_37") (pintype "bidirectional"))
    )
    (net (code "82") (name "unconnected-(U2A-PC7-Pad38)") (class "Default")
      (node (ref "U2") (pin "38") (pinfunction "PC7_38") (pintype "bidirectional"))
    )
    (net (code "83") (name "unconnected-(U2A-PC8-Pad39)") (class "Default")
      (node (ref "U2") (pin "39") (pinfunction "PC8_39") (pintype "bidirectional"))
    )
    (net (code "84") (name "unconnected-(U2A-PC9-Pad40)") (class "Default")
      (node (ref "U2") (pin "40") (pinfunction "PC9_40") (pintype "bidirectional"))
    )
    (net (code "85") (name "unconnected-(U2A-PC10-Pad51)") (class "Default")
      (node (ref "U2") (pin "51") (pinfunction "PC10_51") (pintype "bidirectional"))
    )
    (net (code "86") (name "unconnected-(U2A-PC11-Pad52)") (class "Default")
      (node (ref "U2") (pin "52") (pinfunction "PC11_52") (pintype "bidirectional"))
    )
    (net (code "87") (name "unconnected-(U2A-PC12-Pad53)") (class "Default")
      (node (ref "U2") (pin "53") (pinfunction "PC12_53") (pintype "bidirectional"))
    )
    (net (code "88") (name "unconnected-(U2A-PC13-Pad2)") (class "Default")
      (node (ref "U2") (pin "2") (pinfunction "PC13_2") (pintype "bidirectional"))
    )
    (net (code "89") (name "unconnected-(U2A-PC14-OSC32_IN(PC14)-Pad3)") (class "Default")
      (node (ref "U2") (pin "3") (pinfunction "PC14-OSC32_IN(PC14)_3") (pintype "bidirectional"))
    )
    (net (code "90") (name "unconnected-(U2A-PC15-OSC32_OUT(PC15)-Pad4)") (class "Default")
      (node (ref "U2") (pin "4") (pinfunction "PC15-OSC32_OUT(PC15)_4") (pintype "bidirectional"))
    )
    (net (code "91") (name "unconnected-(U2A-PD2-Pad54)") (class "Default")
      (node (ref "U2") (pin "54") (pinfunction "PD2_54") (pintype "bidirectional"))
    )
    (net (code "92") (name "unconnected-(U4-NC-Pad12)") (class "Default")
      (node (ref "U4") (pin "12") (pinfunction "NC_12") (pintype "passive"))
    )
    (net (code "93") (name "unconnected-(U4-NC-Pad13)") (class "Default")
      (node (ref "U4") (pin "13") (pinfunction "NC_13") (pintype "passive"))
    )
    (net (code "94") (name "unconnected-(U4-NC-Pad28)") (class "Default")
      (node (ref "U4") (pin "28") (pinfunction "NC_28") (pintype "passive"))
    )
    (net (code "95") (name "unconnected-(U4-NC-Pad29)") (class "Default")
      (node (ref "U4") (pin "29") (pinfunction "NC_29") (pintype "passive"))
    )
  )
)
